# PWM_Soldeerbout.net
KiCad netlist of a schematic drawn in Altium Designer
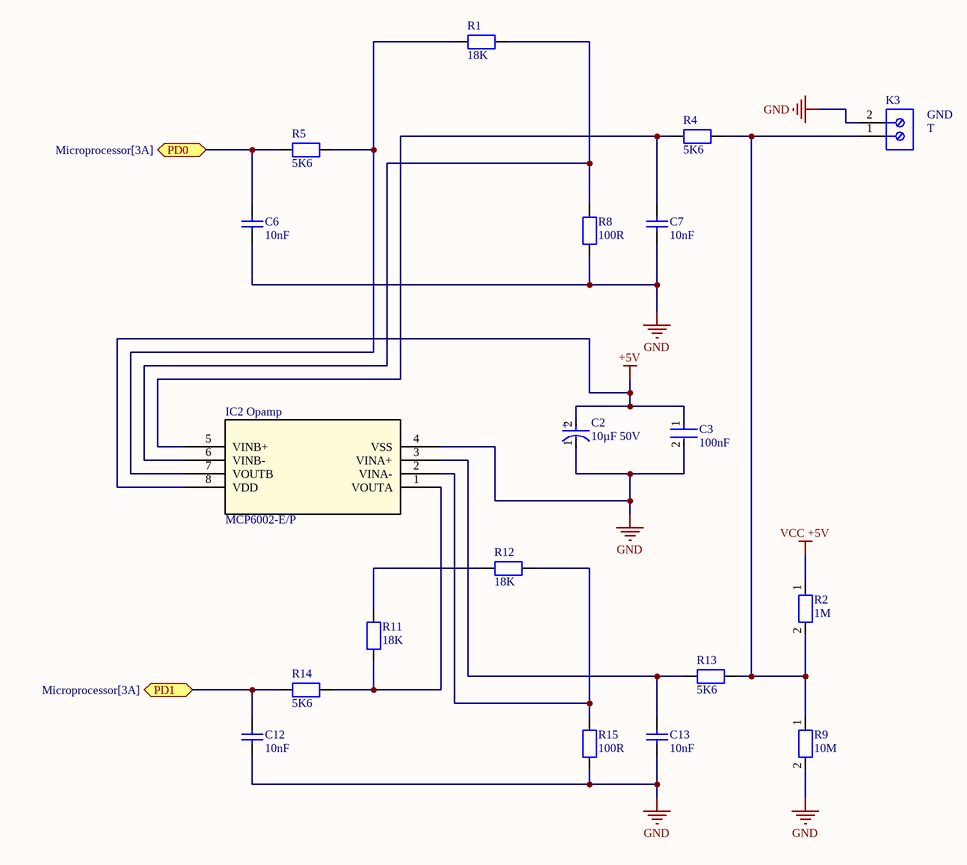
[diagram p0: PWM_Soldeerbout.SchDoc]

(export (version "E")
  (design (tool "Eeschema 10.0.6"))
  (components
    (comp (ref "C2")
      (value "10µF 50V")
      (footprint "cap 10µF 50V")
      (description "Aluminum Electrolytic Capacitors (Radial Lead Type) 10uF ±20% 50V")
      (fields (field (name "TOLERANCE") "20%") (field (name "VOLTAGE") "50V"))
      (libsource (lib "soldeerstation") (part "10µF 50V"))
    )
    (comp (ref "C3")
      (value "100nF")
      (footprint "FP-C0805C-DN-IPC_A")
      (description "Chip Multilayer Ceramic Capacitors for Automotive, 0805, 0.10uF, X7R, 15%, 10%, 50V, Grade 1")
      (fields (field (name "TOLERANCE") "10%"))
      (libsource (lib "soldeerstation") (part "cap 50V 100nF"))
    )
    (comp (ref "C6")
      (value "10nF")
      (footprint "FP-C0805C-DN-IPC_A")
      (fields (field (name "PART NUMBER") "VJ0805Y103KXACW1BC") (field (name "MANUFACTURER") "Vitramon"))
      (libsource (lib "soldeerstation") (part "cap 10nF X7R 50V"))
    )
    (comp (ref "C7")
      (value "10nF")
      (footprint "FP-C0805C-DN-IPC_A")
      (fields (field (name "PART NUMBER") "VJ0805Y103KXACW1BC") (field (name "MANUFACTURER") "Vitramon"))
      (libsource (lib "soldeerstation") (part "cap 10nF X7R 50V"))
    )
    (comp (ref "C12")
      (value "10nF")
      (footprint "FP-C0805C-DN-IPC_A")
      (fields (field (name "PART NUMBER") "VJ0805Y103KXACW1BC") (field (name "MANUFACTURER") "Vitramon"))
      (libsource (lib "soldeerstation") (part "cap 10nF X7R 50V"))
    )
    (comp (ref "C13")
      (value "10nF")
      (footprint "FP-C0805C-DN-IPC_A")
      (fields (field (name "PART NUMBER") "VJ0805Y103KXACW1BC") (field (name "MANUFACTURER") "Vitramon"))
      (libsource (lib "soldeerstation") (part "cap 10nF X7R 50V"))
    )
    (comp (ref "IC2 Opamp")
      (value "MCP6002-E/P")
      (footprint "8pin Socket")
      (description "No Description Available")
      (fields (field (name "COPYRIGHT") "Copyright (C) 2023 Ultra Librarian. All rights reserved."))
      (libsource (lib "soldeerstation") (part "MCP6002-E/P"))
    )
    (comp (ref "K3")
      (value "~")
      (footprint "2pin connector")
      (description "PC Terminal Block, Pitch 6.35 mm, 1 x 2 Position, Height 21.5 mm, Tail Lenght 5.1 mm, RoHS, Bulk")
      (fields (field (name "MANUFACTURER") "Phoenix Contact"))
      (libsource (lib "soldeerstation") (part "Printkroonsteen 2pin"))
    )
    (comp (ref "R1")
      (value "18K")
      (footprint "Weerstand 1M ohm")
      (fields (field (name "PART NUMBER") "CRCW080518K0FKEA") (field (name "MANUFACTURER") "Vishay Dale"))
      (libsource (lib "soldeerstation") (part "Weerstand 18kohm"))
    )
    (comp (ref "R2")
      (value "1M")
      (footprint "Weerstand 1M ohm")
      (description "RES Thick Film, 1MΩ, 1%, 0.125W, 100ppm/°C, 0805")
      (fields (field (name "TOLERANCE") "1%"))
      (libsource (lib "soldeerstation") (part "Weerstand 1M ohm"))
    )
    (comp (ref "R4")
      (value "5K6")
      (footprint "Weerstand 1M ohm")
      (description "5K6 0.125W 5% 0805 (2012 Metric)  SMD")
      (fields (field (name "TOLERANCE") "5 %") (field (name "POWER") "0.125 W"))
      (libsource (lib "soldeerstation") (part "Weerstand 5K6"))
    )
    (comp (ref "R5")
      (value "5K6")
      (footprint "Weerstand 1M ohm")
      (description "5K6 0.125W 5% 0805 (2012 Metric)  SMD")
      (fields (field (name "TOLERANCE") "5 %") (field (name "POWER") "0.125 W"))
      (libsource (lib "soldeerstation") (part "Weerstand 5K6"))
    )
    (comp (ref "R8")
      (value "100R")
      (footprint "Weerstand 1M ohm")
      (fields (field (name "MANUFACTURER") "Vishay Dale") (field (name "PART NUMBER") "CRCW0805100RFKEA"))
      (libsource (lib "soldeerstation") (part "Weerstand 100 ohm"))
    )
    (comp (ref "R9")
      (value "10M")
      (footprint "Weerstand 1M ohm")
      (description "RES Thick Film, 10MΩ, 1%, 0.125W, 100ppm/°C, 0805")
      (fields (field (name "TOLERANCE") "5%"))
      (libsource (lib "soldeerstation") (part "Weerstand 10M ohm"))
    )
    (comp (ref "R11")
      (value "18K")
      (footprint "Weerstand 1M ohm")
      (fields (field (name "PART NUMBER") "CRCW080518K0FKEA") (field (name "MANUFACTURER") "Vishay Dale"))
      (libsource (lib "soldeerstation") (part "Weerstand 18kohm"))
    )
    (comp (ref "R12")
      (value "18K")
      (footprint "Weerstand 1M ohm")
      (fields (field (name "PART NUMBER") "CRCW080518K0FKEA") (field (name "MANUFACTURER") "Vishay Dale"))
      (libsource (lib "soldeerstation") (part "Weerstand 18kohm"))
    )
    (comp (ref "R13")
      (value "5K6")
      (footprint "Weerstand 1M ohm")
      (description "5K6 0.125W 5% 0805 (2012 Metric)  SMD")
      (fields (field (name "TOLERANCE") "5 %") (field (name "POWER") "0.125 W"))
      (libsource (lib "soldeerstation") (part "Weerstand 5K6"))
    )
    (comp (ref "R14")
      (value "5K6")
      (footprint "Weerstand 1M ohm")
      (description "5K6 0.125W 5% 0805 (2012 Metric)  SMD")
      (fields (field (name "TOLERANCE") "5 %") (field (name "POWER") "0.125 W"))
      (libsource (lib "soldeerstation") (part "Weerstand 5K6"))
    )
    (comp (ref "R15")
      (value "100R")
      (footprint "Weerstand 1M ohm")
      (fields (field (name "MANUFACTURER") "Vishay Dale") (field (name "PART NUMBER") "CRCW0805100RFKEA"))
      (libsource (lib "soldeerstation") (part "Weerstand 100 ohm"))
    )
  )
  (nets
    (net (code "1") (name "+5V") (class "Default")
      (node (ref "C2") (pin "2") (pinfunction "A_2") (pintype "passive"))
      (node (ref "C3") (pin "1") (pinfunction "1_1") (pintype "passive"))
      (node (ref "IC2 Opamp") (pin "8") (pinfunction "VDD_8") (pintype "passive"))
    )
    (net (code "2") (name "/PD0") (class "Default")
      (node (ref "C6") (pin "2") (pinfunction "2_2") (pintype "passive"))
      (node (ref "R5") (pin "1") (pinfunction "1_1") (pintype "passive"))
    )
    (net (code "3") (name "/PD1") (class "Default")
      (node (ref "C12") (pin "2") (pinfunction "2_2") (pintype "passive"))
      (node (ref "R14") (pin "1") (pinfunction "1_1") (pintype "passive"))
    )
    (net (code "4") (name "GND") (class "Default")
      (node (ref "C12") (pin "1") (pinfunction "1_1") (pintype "passive"))
      (node (ref "C13") (pin "1") (pinfunction "1_1") (pintype "passive"))
      (node (ref "C2") (pin "1") (pinfunction "C_1") (pintype "passive"))
      (node (ref "C3") (pin "2") (pinfunction "2_2") (pintype "passive"))
      (node (ref "C6") (pin "1") (pinfunction "1_1") (pintype "passive"))
      (node (ref "C7") (pin "1") (pinfunction "1_1") (pintype "passive"))
      (node (ref "IC2 Opamp") (pin "4") (pinfunction "VSS_4") (pintype "passive"))
      (node (ref "K3") (pin "2") (pinfunction "2_2") (pintype "passive"))
      (node (ref "R15") (pin "1") (pinfunction "1_1") (pintype "passive"))
      (node (ref "R8") (pin "1") (pinfunction "1_1") (pintype "passive"))
      (node (ref "R9") (pin "2") (pinfunction "2_2") (pintype "passive"))
    )
    (net (code "5") (name "Net-(IC2 Opamp-VINA+)") (class "Default")
      (node (ref "C13") (pin "2") (pinfunction "2_2") (pintype "passive"))
      (node (ref "IC2 Opamp") (pin "3") (pinfunction "VINA+_3") (pintype "passive"))
      (node (ref "R13") (pin "1") (pinfunction "1_1") (pintype "passive"))
    )
    (net (code "6") (name "Net-(IC2 Opamp-VINA-)") (class "Default")
      (node (ref "IC2 Opamp") (pin "2") (pinfunction "VINA-_2") (pintype "passive"))
      (node (ref "R12") (pin "2") (pinfunction "2_2") (pintype "passive"))
      (node (ref "R15") (pin "2") (pinfunction "2_2") (pintype "passive"))
    )
    (net (code "7") (name "Net-(IC2 Opamp-VINB+)") (class "Default")
      (node (ref "C7") (pin "2") (pinfunction "2_2") (pintype "passive"))
      (node (ref "IC2 Opamp") (pin "5") (pinfunction "VINB+_5") (pintype "passive"))
      (node (ref "R4") (pin "1") (pinfunction "1_1") (pintype "passive"))
    )
    (net (code "8") (name "Net-(IC2 Opamp-VINB-)") (class "Default")
      (node (ref "IC2 Opamp") (pin "6") (pinfunction "VINB-_6") (pintype "passive"))
      (node (ref "R1") (pin "2") (pinfunction "2_2") (pintype "passive"))
      (node (ref "R8") (pin "2") (pinfunction "2_2") (pintype "passive"))
    )
    (net (code "9") (name "Net-(IC2 Opamp-VOUTA)") (class "Default")
      (node (ref "IC2 Opamp") (pin "1") (pinfunction "VOUTA_1") (pintype "passive"))
      (node (ref "R11") (pin "1") (pinfunction "1_1") (pintype "passive"))
      (node (ref "R14") (pin "2") (pinfunction "2_2") (pintype "passive"))
    )
    (net (code "10") (name "Net-(IC2 Opamp-VOUTB)") (class "Default")
      (node (ref "IC2 Opamp") (pin "7") (pinfunction "VOUTB_7") (pintype "passive"))
      (node (ref "R1") (pin "1") (pinfunction "1_1") (pintype "passive"))
      (node (ref "R5") (pin "2") (pinfunction "2_2") (pintype "passive"))
    )
    (net (code "11") (name "Net-(K3-Pad1)") (class "Default")
      (node (ref "K3") (pin "1") (pinfunction "1_1") (pintype "passive"))
      (node (ref "R13") (pin "2") (pinfunction "2_2") (pintype "passive"))
      (node (ref "R2") (pin "2") (pinfunction "2_2") (pintype "passive"))
      (node (ref "R4") (pin "2") (pinfunction "2_2") (pintype "passive"))
      (node (ref "R9") (pin "1") (pinfunction "1_1") (pintype "passive"))
    )
    (net (code "12") (name "Net-(R11-Pad2)") (class "Default")
      (node (ref "R11") (pin "2") (pinfunction "2_2") (pintype "passive"))
      (node (ref "R12") (pin "1") (pinfunction "1_1") (pintype "passive"))
    )
    (net (code "13") (name "VCC +5V") (class "Default")
      (node (ref "R2") (pin "1") (pinfunction "1_1") (pintype "passive"))
    )
  )
)
